# RIGHT_CCM.net
KiCad netlist of a schematic drawn in Altium Designer
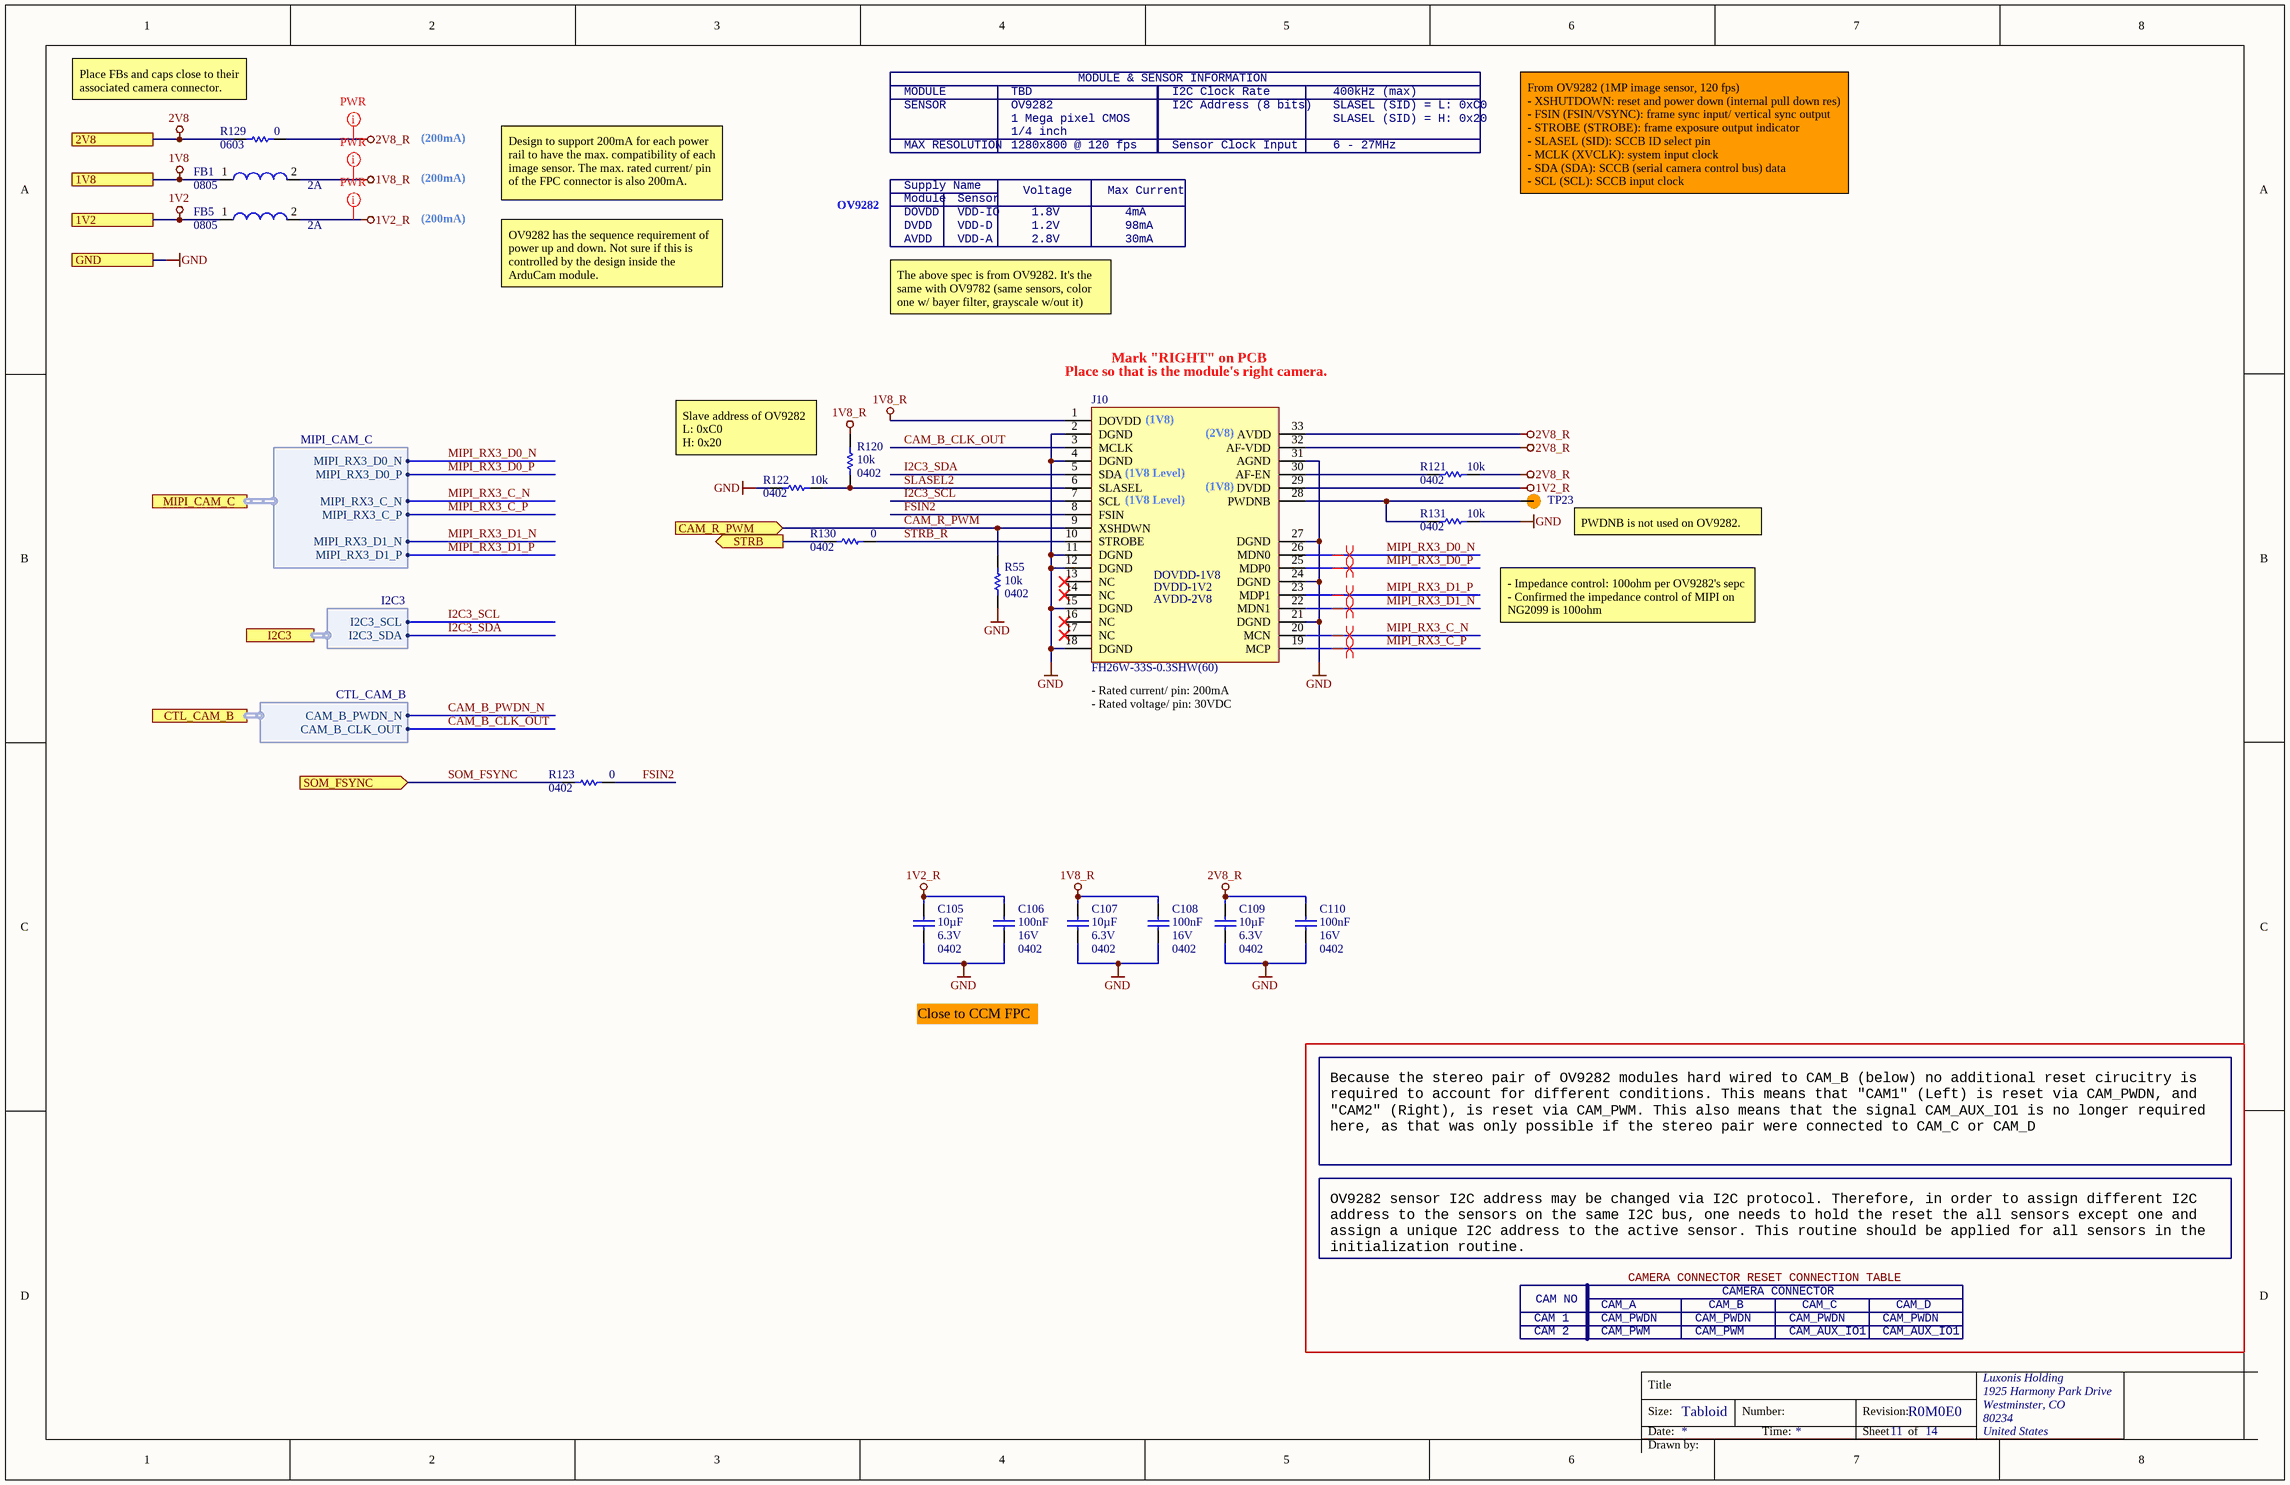
[diagram p0: RIGHT_CCM.SchDoc]

(export (version "E")
  (design (tool "Eeschema 10.0.6"))
  (components
    (comp (ref "C105")
      (value "10µF")
      (footprint "CAPC0402(1005)70_N")
      (description "CAP CER 10UF 6.3V X5R 0402 20%")
      (fields
        (field (name "VOLTAGE RATING") "6.3V")
        (field (name "CASE/PACKAGE") "0402")
        (field (name "TOLERANCE") "20%")
        (field (name "Comment") "GRM155R60J106ME15D")
      )
      (libsource (lib "Luxonis LLC") (part "LLL153C70G474ME17E"))
    )
    (comp (ref "C106")
      (value "100nF")
      (footprint "CAPC0402(1005)60_N")
      (description "CAP CER 0.1UF 16V X7R 0402 10%")
      (fields
        (field (name "VOLTAGE RATING") "16V")
        (field (name "CASE/PACKAGE") "0402")
        (field (name "TOLERANCE") "10%")
        (field (name "Comment") "CL05B104KO5NFNC")
      )
      (libsource (lib "Luxonis LLC") (part "GRM188R61C475KAAJD"))
    )
    (comp (ref "C107")
      (value "10µF")
      (footprint "CAPC0402(1005)70_N")
      (description "CAP CER 10UF 6.3V X5R 0402 20%")
      (fields
        (field (name "VOLTAGE RATING") "6.3V")
        (field (name "CASE/PACKAGE") "0402")
        (field (name "TOLERANCE") "20%")
        (field (name "Comment") "GRM155R60J106ME15D")
      )
      (libsource (lib "Luxonis LLC") (part "LLL153C70G474ME17E"))
    )
    (comp (ref "C108")
      (value "100nF")
      (footprint "CAPC0402(1005)60_N")
      (description "CAP CER 0.1UF 16V X7R 0402 10%")
      (fields
        (field (name "VOLTAGE RATING") "16V")
        (field (name "CASE/PACKAGE") "0402")
        (field (name "TOLERANCE") "10%")
        (field (name "Comment") "CL05B104KO5NFNC")
      )
      (libsource (lib "Luxonis LLC") (part "GRM188R61C475KAAJD"))
    )
    (comp (ref "C109")
      (value "10µF")
      (footprint "CAPC0402(1005)70_N")
      (description "CAP CER 10UF 6.3V X5R 0402 20%")
      (fields
        (field (name "VOLTAGE RATING") "6.3V")
        (field (name "CASE/PACKAGE") "0402")
        (field (name "TOLERANCE") "20%")
        (field (name "Comment") "GRM155R60J106ME15D")
      )
      (libsource (lib "Luxonis LLC") (part "LLL153C70G474ME17E"))
    )
    (comp (ref "C110")
      (value "100nF")
      (footprint "CAPC0402(1005)60_N")
      (description "CAP CER 0.1UF 16V X7R 0402 10%")
      (fields
        (field (name "VOLTAGE RATING") "16V")
        (field (name "CASE/PACKAGE") "0402")
        (field (name "TOLERANCE") "10%")
        (field (name "Comment") "CL05B104KO5NFNC")
      )
      (libsource (lib "Luxonis LLC") (part "GRM188R61C475KAAJD"))
    )
    (comp (ref "FB1")
      (value "2508056017Y2")
      (footprint "2508056017Y2")
      (description "FERRITE BEAD, 0.1OHM, 2A, 0805, 600R/100MHz")
      (fields
        (field (name "CURRENT RATING") "2A")
        (field (name "CASE/PACKAGE") "0805")
        (field (name "TOLERANCE") "25%")
      )
      (libsource (lib "Luxonis LLC") (part "2508056017Y2"))
    )
    (comp (ref "FB5")
      (value "2508056017Y2")
      (footprint "2508056017Y2")
      (description "FERRITE BEAD, 0.1OHM, 2A, 0805, 600R/100MHz")
      (fields
        (field (name "CURRENT RATING") "2A")
        (field (name "CASE/PACKAGE") "0805")
        (field (name "TOLERANCE") "25%")
      )
      (libsource (lib "Luxonis LLC") (part "2508056017Y2"))
    )
    (comp (ref "J10")
      (value "FH26W-33S-0.3SHW(60)")
      (footprint "AC-PY003-OV9282")
      (description "FFC/FPC Connector, 33 Contact(s), 1 Row(s), Female, Right Angle, Surface Mount Terminal")
      (libsource (lib "LuxonisMaster") (part "AC_PY003-OV9282_CON"))
    )
    (comp (ref "R55")
      (value "10k")
      (footprint "RESC0402(1005)_N")
      (description "RES SMD 10K OHM 1% 1/16W 0402")
      (fields
        (field (name "CASE/PACKAGE") "0402")
        (field (name "TOLERANCE") "1%")
        (field (name "Comment") "RC0402FR-1310KL")
      )
      (libsource (lib "Luxonis LLC") (part "RC0402FR-0722RL_1"))
    )
    (comp (ref "R120")
      (value "10k")
      (footprint "RESC0402(1005)_N")
      (description "RES SMD 10K OHM 1% 1/16W 0402")
      (fields
        (field (name "CASE/PACKAGE") "0402")
        (field (name "TOLERANCE") "1%")
        (field (name "Comment") "RC0402FR-1310KL")
      )
      (libsource (lib "Luxonis LLC") (part "RC0402FR-0722RL_1"))
    )
    (comp (ref "R121")
      (value "10k")
      (footprint "RESC0402(1005)_N")
      (description "RES SMD 10K OHM 1% 1/16W 0402")
      (fields
        (field (name "CASE/PACKAGE") "0402")
        (field (name "TOLERANCE") "1%")
        (field (name "Comment") "RC0402FR-1310KL")
      )
      (libsource (lib "Luxonis LLC") (part "RC0402FR-0722RL_1"))
    )
    (comp (ref "R122")
      (value "10k")
      (footprint "RESC0402(1005)_N")
      (description "RES SMD 10K OHM 1% 1/16W 0402")
      (fields
        (field (name "CASE/PACKAGE") "0402")
        (field (name "TOLERANCE") "1%")
        (field (name "Comment") "RC0402FR-1310KL")
      )
      (libsource (lib "Luxonis LLC") (part "RC0402FR-0722RL_1"))
    )
    (comp (ref "R123")
      (value "0")
      (footprint "RESC0402(1005)_L")
      (description "RES SMD 0 OHM 5% 1/16W 0402")
      (fields
        (field (name "CASE/PACKAGE") "0402")
        (field (name "TOLERANCE") "5%")
        (field (name "Comment") "CRCW04020000Z0ED")
      )
      (libsource (lib "Luxonis LLC") (part "Default resistor symbol"))
    )
    (comp (ref "R129")
      (value "0")
      (footprint "RESC0603(1608)_N")
      (description "RES SMD 0 OHM 5% 1/10W 0603")
      (fields
        (field (name "TOLERANCE") "5%")
        (field (name "CASE/PACKAGE") "0603")
        (field (name "Comment") "CRCW06030000Z0EA")
      )
      (libsource (lib "Luxonis LLC") (part "RC0402FR-0722RL_1"))
    )
    (comp (ref "R130")
      (value "0")
      (footprint "RESC0402(1005)_L")
      (description "RES SMD 0 OHM 5% 1/16W 0402")
      (fields
        (field (name "CASE/PACKAGE") "0402")
        (field (name "TOLERANCE") "5%")
        (field (name "Comment") "CRCW04020000Z0ED")
      )
      (libsource (lib "Luxonis LLC") (part "Default resistor symbol"))
    )
    (comp (ref "R131")
      (value "10k")
      (footprint "RESC0402(1005)_N")
      (description "RES SMD 10K OHM 1% 1/16W 0402")
      (fields
        (field (name "CASE/PACKAGE") "0402")
        (field (name "TOLERANCE") "1%")
        (field (name "Comment") "RC0402FR-1310KL")
      )
      (libsource (lib "Luxonis LLC") (part "RC0402FR-0722RL_1"))
    )
    (comp (ref "TP23")
      (value "TP075_150_NS")
      (footprint "LuxonisMaster:TP075_150_NS")
      (libsource (lib "LuxonisMaster") (part "TEST_POINT"))
    )
  )
  (nets
    (net (code "4") (name "/CAM_B_CLK_OUT") (class "Default")
      (node (ref "J10") (pin "3") (pinfunction "MCLK_3") (pintype "passive"))
    )
    (net (code "6") (name "/CAM_R_PWM") (class "Default")
      (node (ref "J10") (pin "9") (pinfunction "XSHDWN_9") (pintype "passive"))
      (node (ref "R55") (pin "2") (pinfunction "2_2") (pintype "passive"))
    )
    (net (code "7") (name "/FSIN2") (class "Default")
      (node (ref "J10") (pin "8") (pinfunction "FSIN_8") (pintype "passive"))
      (node (ref "R123") (pin "1") (pinfunction "1_1") (pintype "passive"))
    )
    (net (code "8") (name "/I2C3_SCL") (class "Default")
      (node (ref "J10") (pin "7") (pinfunction "SCL_7") (pintype "passive"))
    )
    (net (code "9") (name "/I2C3_SDA") (class "Default")
      (node (ref "J10") (pin "5") (pinfunction "SDA_5") (pintype "passive"))
    )
    (net (code "10") (name "/MIPI_RX3_C_N") (class "Default")
      (node (ref "J10") (pin "20") (pinfunction "MCN_20") (pintype "passive"))
    )
    (net (code "11") (name "/MIPI_RX3_C_P") (class "Default")
      (node (ref "J10") (pin "19") (pinfunction "MCP_19") (pintype "passive"))
    )
    (net (code "12") (name "/MIPI_RX3_D0_N") (class "Default")
      (node (ref "J10") (pin "26") (pinfunction "MDN0_26") (pintype "passive"))
    )
    (net (code "13") (name "/MIPI_RX3_D0_P") (class "Default")
      (node (ref "J10") (pin "25") (pinfunction "MDP0_25") (pintype "passive"))
    )
    (net (code "14") (name "/MIPI_RX3_D1_N") (class "Default")
      (node (ref "J10") (pin "22") (pinfunction "MDN1_22") (pintype "passive"))
    )
    (net (code "15") (name "/MIPI_RX3_D1_P") (class "Default")
      (node (ref "J10") (pin "23") (pinfunction "MDP1_23") (pintype "passive"))
    )
    (net (code "16") (name "/SLASEL2") (class "Default")
      (node (ref "J10") (pin "6") (pinfunction "SLASEL_6") (pintype "passive"))
      (node (ref "R120") (pin "1") (pinfunction "1_1") (pintype "passive"))
      (node (ref "R122") (pin "2") (pinfunction "2_2") (pintype "passive"))
    )
    (net (code "17") (name "/SOM_FSYNC") (class "Default")
      (node (ref "R123") (pin "2") (pinfunction "2_2") (pintype "passive"))
    )
    (net (code "18") (name "/STRB") (class "Default")
      (node (ref "R130") (pin "2") (pinfunction "2_2") (pintype "passive"))
    )
    (net (code "19") (name "/STRB_R") (class "Default")
      (node (ref "J10") (pin "10") (pinfunction "STROBE_10") (pintype "passive"))
      (node (ref "R130") (pin "1") (pinfunction "1_1") (pintype "passive"))
    )
    (net (code "23") (name "1V2") (class "Default")
      (node (ref "FB5") (pin "1") (pinfunction "1_1") (pintype "passive"))
    )
    (net (code "24") (name "1V2_R") (class "Default")
      (node (ref "C105") (pin "2") (pinfunction "2_2") (pintype "passive"))
      (node (ref "C106") (pin "2") (pinfunction "2_2") (pintype "passive"))
      (node (ref "FB5") (pin "2") (pinfunction "2_2") (pintype "passive"))
      (node (ref "J10") (pin "29") (pinfunction "DVDD_29") (pintype "passive"))
    )
    (net (code "25") (name "1V8") (class "Default")
      (node (ref "FB1") (pin "1") (pinfunction "1_1") (pintype "passive"))
    )
    (net (code "26") (name "1V8_R") (class "Default")
      (node (ref "C107") (pin "2") (pinfunction "2_2") (pintype "passive"))
      (node (ref "C108") (pin "2") (pinfunction "2_2") (pintype "passive"))
      (node (ref "FB1") (pin "2") (pinfunction "2_2") (pintype "passive"))
      (node (ref "J10") (pin "1") (pinfunction "DOVDD_1") (pintype "passive"))
      (node (ref "R120") (pin "2") (pinfunction "2_2") (pintype "passive"))
    )
    (net (code "27") (name "2V8") (class "Default")
      (node (ref "R129") (pin "1") (pinfunction "1_1") (pintype "passive"))
    )
    (net (code "28") (name "2V8_R") (class "Default")
      (node (ref "C109") (pin "2") (pinfunction "2_2") (pintype "passive"))
      (node (ref "C110") (pin "2") (pinfunction "2_2") (pintype "passive"))
      (node (ref "J10") (pin "32") (pinfunction "AF-VDD_32") (pintype "passive"))
      (node (ref "J10") (pin "33") (pinfunction "AVDD_33") (pintype "passive"))
      (node (ref "R121") (pin "2") (pinfunction "2_2") (pintype "passive"))
      (node (ref "R129") (pin "2") (pinfunction "2_2") (pintype "passive"))
    )
    (net (code "29") (name "GND") (class "Default")
      (node (ref "C105") (pin "1") (pinfunction "1_1") (pintype "passive"))
      (node (ref "C106") (pin "1") (pinfunction "1_1") (pintype "passive"))
      (node (ref "C107") (pin "1") (pinfunction "1_1") (pintype "passive"))
      (node (ref "C108") (pin "1") (pinfunction "1_1") (pintype "passive"))
      (node (ref "C109") (pin "1") (pinfunction "1_1") (pintype "passive"))
      (node (ref "C110") (pin "1") (pinfunction "1_1") (pintype "passive"))
      (node (ref "J10") (pin "11") (pinfunction "DGND_11") (pintype "passive"))
      (node (ref "J10") (pin "12") (pinfunction "DGND_12") (pintype "passive"))
      (node (ref "J10") (pin "15") (pinfunction "DGND_15") (pintype "passive"))
      (node (ref "J10") (pin "18") (pinfunction "DGND_18") (pintype "passive"))
      (node (ref "J10") (pin "2") (pinfunction "DGND_2") (pintype "passive"))
      (node (ref "J10") (pin "21") (pinfunction "DGND_21") (pintype "passive"))
      (node (ref "J10") (pin "24") (pinfunction "DGND_24") (pintype "passive"))
      (node (ref "J10") (pin "27") (pinfunction "DGND_27") (pintype "passive"))
      (node (ref "J10") (pin "31") (pinfunction "AGND_31") (pintype "passive"))
      (node (ref "J10") (pin "4") (pinfunction "DGND_4") (pintype "passive"))
      (node (ref "R122") (pin "1") (pinfunction "1_1") (pintype "passive"))
      (node (ref "R131") (pin "2") (pinfunction "2_2") (pintype "passive"))
      (node (ref "R55") (pin "1") (pinfunction "1_1") (pintype "passive"))
    )
    (net (code "30") (name "Net-(J10-AF-EN)") (class "Default")
      (node (ref "J10") (pin "30") (pinfunction "AF-EN_30") (pintype "passive"))
      (node (ref "R121") (pin "1") (pinfunction "1_1") (pintype "passive"))
    )
    (net (code "31") (name "Net-(J10-PWDNB)") (class "Default")
      (node (ref "J10") (pin "28") (pinfunction "PWDNB_28") (pintype "passive"))
      (node (ref "R131") (pin "1") (pinfunction "1_1") (pintype "passive"))
      (node (ref "TP23") (pin "1") (pintype "passive"))
    )
    (net (code "32") (name "unconnected-(J10-NC-Pad13)") (class "Default")
      (node (ref "J10") (pin "13") (pinfunction "NC_13") (pintype "passive+no_connect"))
    )
    (net (code "33") (name "unconnected-(J10-NC-Pad14)") (class "Default")
      (node (ref "J10") (pin "14") (pinfunction "NC_14") (pintype "passive+no_connect"))
    )
    (net (code "34") (name "unconnected-(J10-NC-Pad16)") (class "Default")
      (node (ref "J10") (pin "16") (pinfunction "NC_16") (pintype "passive+no_connect"))
    )
    (net (code "35") (name "unconnected-(J10-NC-Pad17)") (class "Default")
      (node (ref "J10") (pin "17") (pinfunction "NC_17") (pintype "passive+no_connect"))
    )
  )
)
